# IKCM30F60GD.net
KiCad netlist of a schematic drawn in Altium Designer
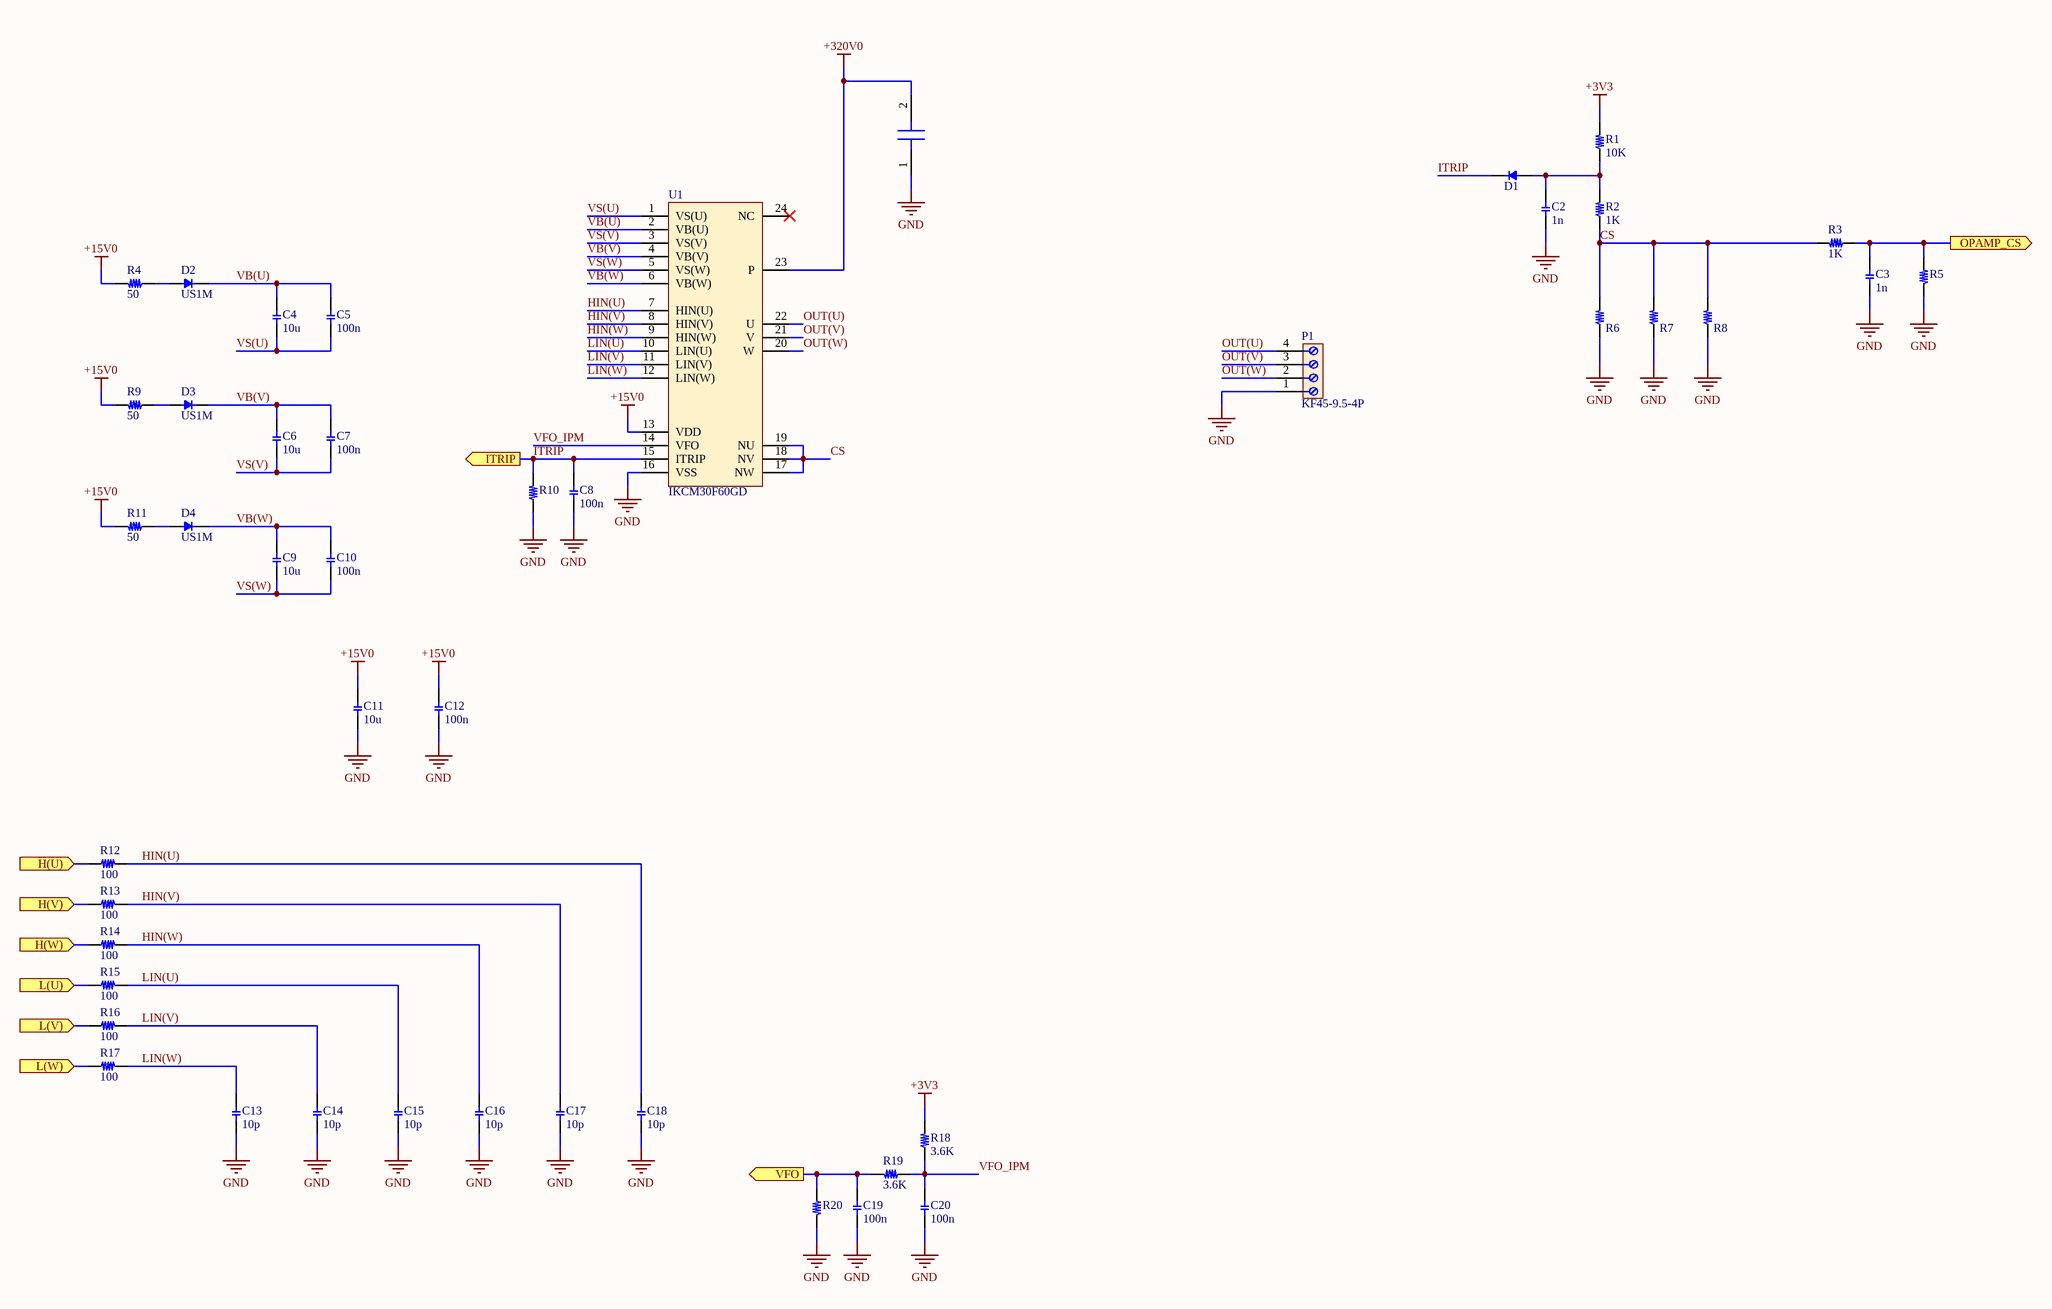
[diagram p0: IKCM30F60GD.SchDoc]

(export (version "E")
  (design (tool "Eeschema 10.0.6"))
  (components
    (comp (ref "C1") (value "CAP") (footprint "C FILM 15mm") (libsource (lib "radmehr_library") (part "CAP")))
    (comp (ref "C2")
      (value "1n")
      (footprint "C 0603")
      (description "CAP_SMD")
      (libsource (lib "radmehr_library") (part "CAP_SMD"))
    )
    (comp (ref "C3")
      (value "1n")
      (footprint "C 0603")
      (description "CAP_SMD")
      (libsource (lib "radmehr_library") (part "CAP_SMD"))
    )
    (comp (ref "C4")
      (value "10u")
      (footprint "C 0603")
      (description "CAP_SMD")
      (libsource (lib "radmehr_library") (part "CAP_SMD"))
    )
    (comp (ref "C5")
      (value "100n")
      (footprint "C 0603")
      (description "CAP_SMD")
      (libsource (lib "radmehr_library") (part "CAP_SMD"))
    )
    (comp (ref "C6")
      (value "10u")
      (footprint "C 0603")
      (description "CAP_SMD")
      (libsource (lib "radmehr_library") (part "CAP_SMD"))
    )
    (comp (ref "C7")
      (value "100n")
      (footprint "C 0603")
      (description "CAP_SMD")
      (libsource (lib "radmehr_library") (part "CAP_SMD"))
    )
    (comp (ref "C8")
      (value "100n")
      (footprint "C 0603")
      (description "CAP_SMD")
      (libsource (lib "radmehr_library") (part "CAP_SMD"))
    )
    (comp (ref "C9")
      (value "10u")
      (footprint "C 0603")
      (description "CAP_SMD")
      (libsource (lib "radmehr_library") (part "CAP_SMD"))
    )
    (comp (ref "C10")
      (value "100n")
      (footprint "C 0603")
      (description "CAP_SMD")
      (libsource (lib "radmehr_library") (part "CAP_SMD"))
    )
    (comp (ref "C11")
      (value "10u")
      (footprint "C 0603")
      (description "CAP_SMD")
      (libsource (lib "radmehr_library") (part "CAP_SMD"))
    )
    (comp (ref "C12")
      (value "100n")
      (footprint "C 0603")
      (description "CAP_SMD")
      (libsource (lib "radmehr_library") (part "CAP_SMD"))
    )
    (comp (ref "C13")
      (value "10p")
      (footprint "C 0603")
      (description "CAP_SMD")
      (libsource (lib "radmehr_library") (part "CAP_SMD"))
    )
    (comp (ref "C14")
      (value "10p")
      (footprint "C 0603")
      (description "CAP_SMD")
      (libsource (lib "radmehr_library") (part "CAP_SMD"))
    )
    (comp (ref "C15")
      (value "10p")
      (footprint "C 0603")
      (description "CAP_SMD")
      (libsource (lib "radmehr_library") (part "CAP_SMD"))
    )
    (comp (ref "C16")
      (value "10p")
      (footprint "C 0603")
      (description "CAP_SMD")
      (libsource (lib "radmehr_library") (part "CAP_SMD"))
    )
    (comp (ref "C17")
      (value "10p")
      (footprint "C 0603")
      (description "CAP_SMD")
      (libsource (lib "radmehr_library") (part "CAP_SMD"))
    )
    (comp (ref "C18")
      (value "10p")
      (footprint "C 0603")
      (description "CAP_SMD")
      (libsource (lib "radmehr_library") (part "CAP_SMD"))
    )
    (comp (ref "C19")
      (value "100n")
      (footprint "C 0603")
      (description "CAP_SMD")
      (libsource (lib "radmehr_library") (part "CAP_SMD"))
    )
    (comp (ref "C20")
      (value "100n")
      (footprint "C 0603")
      (description "CAP_SMD")
      (libsource (lib "radmehr_library") (part "CAP_SMD"))
    )
    (comp (ref "D1")
      (value "DIOD_SMD")
      (footprint "D SOD-323")
      (libsource (lib "radmehr_library") (part "DIOD_SMD"))
    )
    (comp (ref "D2")
      (value "US1M")
      (footprint "DIOD_SMA")
      (description "DIOD_SMD")
      (libsource (lib "radmehr_library") (part "DIOD_SMD"))
    )
    (comp (ref "D3")
      (value "US1M")
      (footprint "DIOD_SMA")
      (description "DIOD_SMD")
      (libsource (lib "radmehr_library") (part "DIOD_SMD"))
    )
    (comp (ref "D4")
      (value "US1M")
      (footprint "DIOD_SMA")
      (description "DIOD_SMD")
      (libsource (lib "radmehr_library") (part "DIOD_SMD"))
    )
    (comp (ref "P1")
      (value "KF45-9.5-4P")
      (footprint "DG45C-B-04P-13")
      (libsource (lib "TERMINAL") (part "KF45-9.5-4P"))
    )
    (comp (ref "R1")
      (value "10K")
      (footprint "R 0603")
      (description "RES_SMD")
      (libsource (lib "radmehr_library") (part "RES_SMD"))
    )
    (comp (ref "R2")
      (value "1K")
      (footprint "R 0603")
      (description "RES_SMD")
      (libsource (lib "radmehr_library") (part "RES_SMD"))
    )
    (comp (ref "R3")
      (value "1K")
      (footprint "R 0603")
      (description "RES_SMD")
      (libsource (lib "radmehr_library") (part "RES_SMD"))
    )
    (comp (ref "R4")
      (value "50")
      (footprint "R 1206")
      (description "RES_SMD")
      (libsource (lib "radmehr_library") (part "RES_SMD"))
    )
    (comp (ref "R5")
      (value "1K")
      (footprint "R 0603")
      (description "RES_SMD")
      (libsource (lib "radmehr_library") (part "RES_SMD"))
    )
    (comp (ref "R6")
      (value "RES_SMD")
      (footprint "R 2512")
      (libsource (lib "radmehr_library") (part "RES_SMD"))
    )
    (comp (ref "R7")
      (value "RES_SMD")
      (footprint "R 2512")
      (libsource (lib "radmehr_library") (part "RES_SMD"))
    )
    (comp (ref "R8")
      (value "RES_SMD")
      (footprint "R 2512")
      (libsource (lib "radmehr_library") (part "RES_SMD"))
    )
    (comp (ref "R9")
      (value "50")
      (footprint "R 1206")
      (description "RES_SMD")
      (libsource (lib "radmehr_library") (part "RES_SMD"))
    )
    (comp (ref "R10")
      (value "1K")
      (footprint "R 0603")
      (description "RES_SMD")
      (libsource (lib "radmehr_library") (part "RES_SMD"))
    )
    (comp (ref "R11")
      (value "50")
      (footprint "R 1206")
      (description "RES_SMD")
      (libsource (lib "radmehr_library") (part "RES_SMD"))
    )
    (comp (ref "R12")
      (value "100")
      (footprint "R 0603")
      (description "RES_SMD")
      (libsource (lib "radmehr_library") (part "RES_SMD"))
    )
    (comp (ref "R13")
      (value "100")
      (footprint "R 0603")
      (description "RES_SMD")
      (libsource (lib "radmehr_library") (part "RES_SMD"))
    )
    (comp (ref "R14")
      (value "100")
      (footprint "R 0603")
      (description "RES_SMD")
      (libsource (lib "radmehr_library") (part "RES_SMD"))
    )
    (comp (ref "R15")
      (value "100")
      (footprint "R 0603")
      (description "RES_SMD")
      (libsource (lib "radmehr_library") (part "RES_SMD"))
    )
    (comp (ref "R16")
      (value "100")
      (footprint "R 0603")
      (description "RES_SMD")
      (libsource (lib "radmehr_library") (part "RES_SMD"))
    )
    (comp (ref "R17")
      (value "100")
      (footprint "R 0603")
      (description "RES_SMD")
      (libsource (lib "radmehr_library") (part "RES_SMD"))
    )
    (comp (ref "R18")
      (value "3.6K")
      (footprint "R 0603")
      (description "RES_SMD")
      (libsource (lib "radmehr_library") (part "RES_SMD"))
    )
    (comp (ref "R19")
      (value "3.6K")
      (footprint "R 0603")
      (description "RES_SMD")
      (libsource (lib "radmehr_library") (part "RES_SMD"))
    )
    (comp (ref "R20")
      (value "3.6K")
      (footprint "R 0603")
      (description "RES_SMD")
      (libsource (lib "radmehr_library") (part "RES_SMD"))
    )
    (comp (ref "U1")
      (value "IKCM30F60GD")
      (footprint "INF-CIPOS MINI")
      (libsource (lib "radmehr_library") (part "IKCM30F60GD"))
    )
  )
  (nets
    (net (code "1") (name "+3V3") (class "Default")
      (node (ref "R1") (pin "2") (pinfunction "2_2") (pintype "passive"))
      (node (ref "R18") (pin "2") (pinfunction "2_2") (pintype "passive"))
    )
    (net (code "2") (name "+15V0") (class "Default")
      (node (ref "C11") (pin "2") (pinfunction "2_2") (pintype "passive"))
      (node (ref "C12") (pin "2") (pinfunction "2_2") (pintype "passive"))
      (node (ref "R11") (pin "2") (pinfunction "2_2") (pintype "passive"))
      (node (ref "R4") (pin "2") (pinfunction "2_2") (pintype "passive"))
      (node (ref "R9") (pin "2") (pinfunction "2_2") (pintype "passive"))
      (node (ref "U1") (pin "13") (pinfunction "VDD_13") (pintype "passive"))
    )
    (net (code "3") (name "+320V0") (class "Default")
      (node (ref "C1") (pin "2") (pintype "passive"))
      (node (ref "U1") (pin "23") (pinfunction "P_23") (pintype "passive"))
    )
    (net (code "4") (name "/CS") (class "Default")
      (node (ref "R2") (pin "1") (pinfunction "1_1") (pintype "passive"))
      (node (ref "R3") (pin "2") (pinfunction "2_2") (pintype "passive"))
      (node (ref "R6") (pin "2") (pinfunction "2_2") (pintype "passive"))
      (node (ref "R7") (pin "2") (pinfunction "2_2") (pintype "passive"))
      (node (ref "R8") (pin "2") (pinfunction "2_2") (pintype "passive"))
      (node (ref "U1") (pin "17") (pinfunction "NW_17") (pintype "passive"))
      (node (ref "U1") (pin "18") (pinfunction "NV_18") (pintype "passive"))
      (node (ref "U1") (pin "19") (pinfunction "NU_19") (pintype "passive"))
    )
    (net (code "5") (name "/H(U)") (class "Default")
      (node (ref "R12") (pin "1") (pinfunction "1_1") (pintype "passive"))
    )
    (net (code "6") (name "/H(V)") (class "Default")
      (node (ref "R13") (pin "1") (pinfunction "1_1") (pintype "passive"))
    )
    (net (code "7") (name "/H(W)") (class "Default")
      (node (ref "R14") (pin "1") (pinfunction "1_1") (pintype "passive"))
    )
    (net (code "8") (name "/HIN(U)") (class "Default")
      (node (ref "C18") (pin "2") (pinfunction "2_2") (pintype "passive"))
      (node (ref "R12") (pin "2") (pinfunction "2_2") (pintype "passive"))
      (node (ref "U1") (pin "7") (pinfunction "HIN(U)_7") (pintype "passive"))
    )
    (net (code "9") (name "/HIN(V)") (class "Default")
      (node (ref "C17") (pin "2") (pinfunction "2_2") (pintype "passive"))
      (node (ref "R13") (pin "2") (pinfunction "2_2") (pintype "passive"))
      (node (ref "U1") (pin "8") (pinfunction "HIN(V)_8") (pintype "passive"))
    )
    (net (code "10") (name "/HIN(W)") (class "Default")
      (node (ref "C16") (pin "2") (pinfunction "2_2") (pintype "passive"))
      (node (ref "R14") (pin "2") (pinfunction "2_2") (pintype "passive"))
      (node (ref "U1") (pin "9") (pinfunction "HIN(W)_9") (pintype "passive"))
    )
    (net (code "11") (name "/ITRIP") (class "Default")
      (node (ref "C8") (pin "2") (pinfunction "2_2") (pintype "passive"))
      (node (ref "D1") (pin "2") (pinfunction "2_2") (pintype "passive"))
      (node (ref "R10") (pin "2") (pinfunction "2_2") (pintype "passive"))
      (node (ref "U1") (pin "15") (pinfunction "ITRIP_15") (pintype "passive"))
    )
    (net (code "12") (name "/L(U)") (class "Default")
      (node (ref "R15") (pin "1") (pinfunction "1_1") (pintype "passive"))
    )
    (net (code "13") (name "/L(V)") (class "Default")
      (node (ref "R16") (pin "1") (pinfunction "1_1") (pintype "passive"))
    )
    (net (code "14") (name "/L(W)") (class "Default")
      (node (ref "R17") (pin "1") (pinfunction "1_1") (pintype "passive"))
    )
    (net (code "15") (name "/LIN(U)") (class "Default")
      (node (ref "C15") (pin "2") (pinfunction "2_2") (pintype "passive"))
      (node (ref "R15") (pin "2") (pinfunction "2_2") (pintype "passive"))
      (node (ref "U1") (pin "10") (pinfunction "LIN(U)_10") (pintype "passive"))
    )
    (net (code "16") (name "/LIN(V)") (class "Default")
      (node (ref "C14") (pin "2") (pinfunction "2_2") (pintype "passive"))
      (node (ref "R16") (pin "2") (pinfunction "2_2") (pintype "passive"))
      (node (ref "U1") (pin "11") (pinfunction "LIN(V)_11") (pintype "passive"))
    )
    (net (code "17") (name "/LIN(W)") (class "Default")
      (node (ref "C13") (pin "2") (pinfunction "2_2") (pintype "passive"))
      (node (ref "R17") (pin "2") (pinfunction "2_2") (pintype "passive"))
      (node (ref "U1") (pin "12") (pinfunction "LIN(W)_12") (pintype "passive"))
    )
    (net (code "18") (name "/OPAMP_CS") (class "Default")
      (node (ref "C3") (pin "2") (pinfunction "2_2") (pintype "passive"))
      (node (ref "R3") (pin "1") (pinfunction "1_1") (pintype "passive"))
      (node (ref "R5") (pin "1") (pinfunction "1_1") (pintype "passive"))
    )
    (net (code "19") (name "/OUT(U)") (class "Default")
      (node (ref "P1") (pin "4") (pinfunction "4_4") (pintype "passive"))
      (node (ref "U1") (pin "22") (pinfunction "U_22") (pintype "passive"))
    )
    (net (code "20") (name "/OUT(V)") (class "Default")
      (node (ref "P1") (pin "3") (pinfunction "3_3") (pintype "passive"))
      (node (ref "U1") (pin "21") (pinfunction "V_21") (pintype "passive"))
    )
    (net (code "21") (name "/OUT(W)") (class "Default")
      (node (ref "P1") (pin "2") (pinfunction "2_2") (pintype "passive"))
      (node (ref "U1") (pin "20") (pinfunction "W_20") (pintype "passive"))
    )
    (net (code "22") (name "/VB(U)") (class "Default")
      (node (ref "C4") (pin "2") (pinfunction "2_2") (pintype "passive"))
      (node (ref "C5") (pin "2") (pinfunction "2_2") (pintype "passive"))
      (node (ref "D2") (pin "2") (pinfunction "2_2") (pintype "passive"))
      (node (ref "U1") (pin "2") (pinfunction "VB(U)_2") (pintype "passive"))
    )
    (net (code "23") (name "/VB(V)") (class "Default")
      (node (ref "C6") (pin "2") (pinfunction "2_2") (pintype "passive"))
      (node (ref "C7") (pin "2") (pinfunction "2_2") (pintype "passive"))
      (node (ref "D3") (pin "2") (pinfunction "2_2") (pintype "passive"))
      (node (ref "U1") (pin "4") (pinfunction "VB(V)_4") (pintype "passive"))
    )
    (net (code "24") (name "/VB(W)") (class "Default")
      (node (ref "C10") (pin "2") (pinfunction "2_2") (pintype "passive"))
      (node (ref "C9") (pin "2") (pinfunction "2_2") (pintype "passive"))
      (node (ref "D4") (pin "2") (pinfunction "2_2") (pintype "passive"))
      (node (ref "U1") (pin "6") (pinfunction "VB(W)_6") (pintype "passive"))
    )
    (net (code "25") (name "/VFO") (class "Default")
      (node (ref "C19") (pin "2") (pinfunction "2_2") (pintype "passive"))
      (node (ref "R19") (pin "2") (pinfunction "2_2") (pintype "passive"))
      (node (ref "R20") (pin "1") (pinfunction "1_1") (pintype "passive"))
    )
    (net (code "26") (name "/VFO_IPM") (class "Default")
      (node (ref "C20") (pin "2") (pinfunction "2_2") (pintype "passive"))
      (node (ref "R18") (pin "1") (pinfunction "1_1") (pintype "passive"))
      (node (ref "R19") (pin "1") (pinfunction "1_1") (pintype "passive"))
      (node (ref "U1") (pin "14") (pinfunction "VFO_14") (pintype "passive"))
    )
    (net (code "27") (name "/VS(U)") (class "Default")
      (node (ref "C4") (pin "1") (pinfunction "1_1") (pintype "passive"))
      (node (ref "C5") (pin "1") (pinfunction "1_1") (pintype "passive"))
      (node (ref "U1") (pin "1") (pinfunction "VS(U)_1") (pintype "passive"))
    )
    (net (code "28") (name "/VS(V)") (class "Default")
      (node (ref "C6") (pin "1") (pinfunction "1_1") (pintype "passive"))
      (node (ref "C7") (pin "1") (pinfunction "1_1") (pintype "passive"))
      (node (ref "U1") (pin "3") (pinfunction "VS(V)_3") (pintype "passive"))
    )
    (net (code "29") (name "/VS(W)") (class "Default")
      (node (ref "C10") (pin "1") (pinfunction "1_1") (pintype "passive"))
      (node (ref "C9") (pin "1") (pinfunction "1_1") (pintype "passive"))
      (node (ref "U1") (pin "5") (pinfunction "VS(W)_5") (pintype "passive"))
    )
    (net (code "30") (name "GND") (class "Default")
      (node (ref "C1") (pin "1") (pintype "passive"))
      (node (ref "C11") (pin "1") (pinfunction "1_1") (pintype "passive"))
      (node (ref "C12") (pin "1") (pinfunction "1_1") (pintype "passive"))
      (node (ref "C13") (pin "1") (pinfunction "1_1") (pintype "passive"))
      (node (ref "C14") (pin "1") (pinfunction "1_1") (pintype "passive"))
      (node (ref "C15") (pin "1") (pinfunction "1_1") (pintype "passive"))
      (node (ref "C16") (pin "1") (pinfunction "1_1") (pintype "passive"))
      (node (ref "C17") (pin "1") (pinfunction "1_1") (pintype "passive"))
      (node (ref "C18") (pin "1") (pinfunction "1_1") (pintype "passive"))
      (node (ref "C19") (pin "1") (pinfunction "1_1") (pintype "passive"))
      (node (ref "C2") (pin "1") (pinfunction "1_1") (pintype "passive"))
      (node (ref "C20") (pin "1") (pinfunction "1_1") (pintype "passive"))
      (node (ref "C3") (pin "1") (pinfunction "1_1") (pintype "passive"))
      (node (ref "C8") (pin "1") (pinfunction "1_1") (pintype "passive"))
      (node (ref "P1") (pin "1") (pinfunction "1_1") (pintype "passive"))
      (node (ref "R10") (pin "1") (pinfunction "1_1") (pintype "passive"))
      (node (ref "R20") (pin "2") (pinfunction "2_2") (pintype "passive"))
      (node (ref "R5") (pin "2") (pinfunction "2_2") (pintype "passive"))
      (node (ref "R6") (pin "1") (pinfunction "1_1") (pintype "passive"))
      (node (ref "R7") (pin "1") (pinfunction "1_1") (pintype "passive"))
      (node (ref "R8") (pin "1") (pinfunction "1_1") (pintype "passive"))
      (node (ref "U1") (pin "16") (pinfunction "VSS_16") (pintype "passive"))
    )
    (net (code "31") (name "Net-(C2-Pad2)") (class "Default")
      (node (ref "C2") (pin "2") (pinfunction "2_2") (pintype "passive"))
      (node (ref "D1") (pin "1") (pinfunction "1_1") (pintype "passive"))
      (node (ref "R1") (pin "1") (pinfunction "1_1") (pintype "passive"))
      (node (ref "R2") (pin "2") (pinfunction "2_2") (pintype "passive"))
    )
    (net (code "32") (name "Net-(D2-Pad1)") (class "Default")
      (node (ref "D2") (pin "1") (pinfunction "1_1") (pintype "passive"))
      (node (ref "R4") (pin "1") (pinfunction "1_1") (pintype "passive"))
    )
    (net (code "33") (name "Net-(D3-Pad1)") (class "Default")
      (node (ref "D3") (pin "1") (pinfunction "1_1") (pintype "passive"))
      (node (ref "R9") (pin "1") (pinfunction "1_1") (pintype "passive"))
    )
    (net (code "34") (name "Net-(D4-Pad1)") (class "Default")
      (node (ref "D4") (pin "1") (pinfunction "1_1") (pintype "passive"))
      (node (ref "R11") (pin "1") (pinfunction "1_1") (pintype "passive"))
    )
    (net (code "35") (name "unconnected-(U1-NC-Pad24)") (class "Default")
      (node (ref "U1") (pin "24") (pinfunction "NC_24") (pintype "passive+no_connect"))
    )
  )
)
